# board.net
KiCad netlist of a schematic drawn in EAGLE
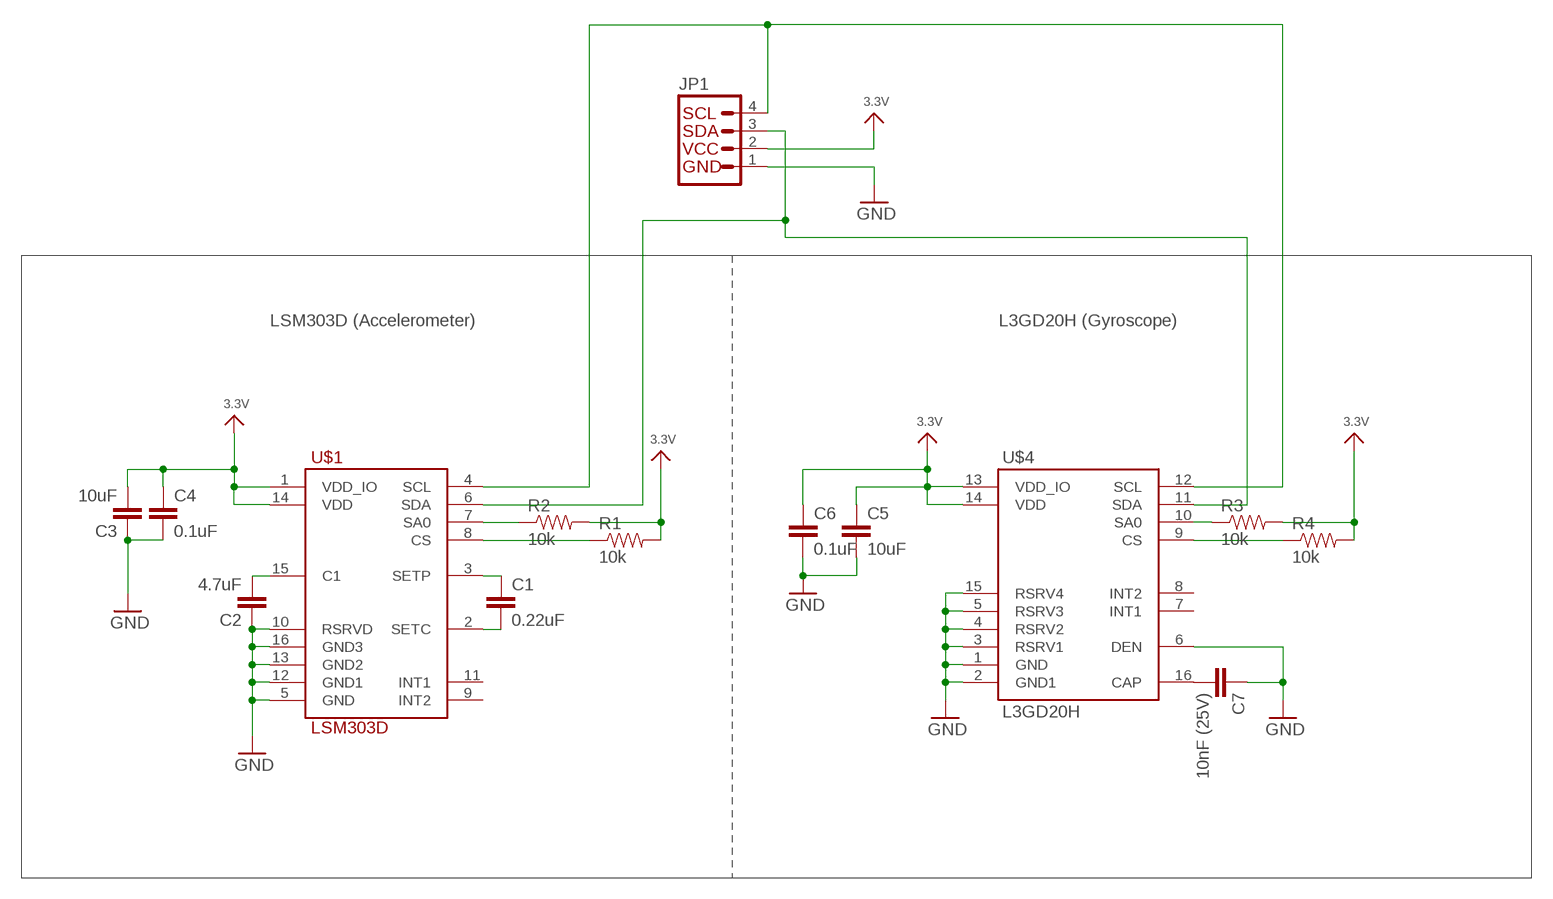
[diagram p0: schematic, sheet 1]

(export (version "E")
  (design (tool "Eeschema 10.0.6"))
  (components
    (comp (ref "C1")
      (value "0.22uF")
      (footprint "eagle-import:0805")
      (libsource (lib "eagle-import") (part "CAP0805"))
    )
    (comp (ref "C2")
      (value "4.7uF")
      (footprint "eagle-import:0805")
      (libsource (lib "eagle-import") (part "CAP0805"))
    )
    (comp (ref "C3")
      (value "10uF")
      (footprint "eagle-import:0805")
      (libsource (lib "eagle-import") (part "CAP0805"))
    )
    (comp (ref "C4")
      (value "0.1uF")
      (footprint "eagle-import:0805")
      (libsource (lib "eagle-import") (part "CAP0805"))
    )
    (comp (ref "C5")
      (value "10uF")
      (footprint "eagle-import:0805")
      (libsource (lib "eagle-import") (part "CAP0805"))
    )
    (comp (ref "C6")
      (value "0.1uF")
      (footprint "eagle-import:0805")
      (libsource (lib "eagle-import") (part "CAP0805"))
    )
    (comp (ref "C7")
      (value "10nF (25V)")
      (footprint "eagle-import:0805")
      (libsource (lib "eagle-import") (part "CAP0805"))
    )
    (comp (ref "JP1")
      (value "I2C_STANDARD")
      (footprint "eagle-import:1X04")
      (libsource (lib "eagle-import") (part "I2C_STANDARD"))
    )
    (comp (ref "R1")
      (value "10k")
      (footprint "eagle-import:0805")
      (libsource (lib "eagle-import") (part "RESISTOR0805-RES"))
    )
    (comp (ref "R2")
      (value "10k")
      (footprint "eagle-import:0805")
      (libsource (lib "eagle-import") (part "RESISTOR0805-RES"))
    )
    (comp (ref "R3")
      (value "10k")
      (footprint "eagle-import:0805")
      (libsource (lib "eagle-import") (part "RESISTOR0805-RES"))
    )
    (comp (ref "R4")
      (value "10k")
      (footprint "eagle-import:0805")
      (libsource (lib "eagle-import") (part "RESISTOR0805-RES"))
    )
    (comp (ref "U$1")
      (value "LSM303D")
      (footprint "eagle-import:LGA16_3X3MM")
      (libsource (lib "eagle-import") (part "LSM303D"))
    )
    (comp (ref "U$4")
      (value "L3GD20H")
      (footprint "eagle-import:LGA16_3X3MM")
      (libsource (lib "eagle-import") (part "L3GD20H"))
    )
  )
  (nets
    (net (code "1") (name "3.3V") (class "Default")
      (node (ref "C3") (pin "2") (pinfunction "2_2") (pintype "passive"))
      (node (ref "C4") (pin "1") (pinfunction "1_1") (pintype "passive"))
      (node (ref "C5") (pin "1") (pinfunction "1_1") (pintype "passive"))
      (node (ref "C6") (pin "1") (pinfunction "1_1") (pintype "passive"))
      (node (ref "JP1") (pin "2") (pinfunction "2_2") (pintype "passive"))
      (node (ref "R1") (pin "2") (pinfunction "2_2") (pintype "passive"))
      (node (ref "R2") (pin "2") (pinfunction "2_2") (pintype "passive"))
      (node (ref "R3") (pin "2") (pinfunction "2_2") (pintype "passive"))
      (node (ref "R4") (pin "2") (pinfunction "2_2") (pintype "passive"))
      (node (ref "U$1") (pin "1") (pinfunction "VDD_IO_1") (pintype "bidirectional"))
      (node (ref "U$1") (pin "14") (pinfunction "VDD_14") (pintype "bidirectional"))
      (node (ref "U$4") (pin "13") (pinfunction "VDD_IO_13") (pintype "bidirectional"))
      (node (ref "U$4") (pin "14") (pinfunction "VDD_14") (pintype "bidirectional"))
    )
    (net (code "2") (name "GND") (class "Default")
      (node (ref "C2") (pin "1") (pinfunction "1_1") (pintype "passive"))
      (node (ref "C3") (pin "1") (pinfunction "1_1") (pintype "passive"))
      (node (ref "C4") (pin "2") (pinfunction "2_2") (pintype "passive"))
      (node (ref "C5") (pin "2") (pinfunction "2_2") (pintype "passive"))
      (node (ref "C6") (pin "2") (pinfunction "2_2") (pintype "passive"))
      (node (ref "C7") (pin "1") (pinfunction "1_1") (pintype "passive"))
      (node (ref "JP1") (pin "1") (pinfunction "1_1") (pintype "passive"))
      (node (ref "U$1") (pin "10") (pinfunction "RSRVD_10") (pintype "bidirectional"))
      (node (ref "U$1") (pin "12") (pinfunction "GND1_12") (pintype "bidirectional"))
      (node (ref "U$1") (pin "13") (pinfunction "GND2_13") (pintype "bidirectional"))
      (node (ref "U$1") (pin "16") (pinfunction "GND3_16") (pintype "bidirectional"))
      (node (ref "U$1") (pin "5") (pinfunction "GND_5") (pintype "bidirectional"))
      (node (ref "U$4") (pin "1") (pinfunction "GND_1") (pintype "bidirectional"))
      (node (ref "U$4") (pin "15") (pinfunction "RSRV4_15") (pintype "bidirectional"))
      (node (ref "U$4") (pin "2") (pinfunction "GND1_2") (pintype "bidirectional"))
      (node (ref "U$4") (pin "3") (pinfunction "RSRV1_3") (pintype "bidirectional"))
      (node (ref "U$4") (pin "4") (pinfunction "RSRV2_4") (pintype "bidirectional"))
      (node (ref "U$4") (pin "5") (pinfunction "RSRV3_5") (pintype "bidirectional"))
      (node (ref "U$4") (pin "6") (pinfunction "DEN_6") (pintype "bidirectional"))
    )
    (net (code "3") (name "Net-(U$1-C1)") (class "Default")
      (node (ref "C2") (pin "2") (pinfunction "2_2") (pintype "passive"))
      (node (ref "U$1") (pin "15") (pinfunction "C1_15") (pintype "bidirectional"))
    )
    (net (code "4") (name "Net-(U$1-CS)") (class "Default")
      (node (ref "R1") (pin "1") (pinfunction "1_1") (pintype "passive"))
      (node (ref "U$1") (pin "8") (pinfunction "CS_8") (pintype "bidirectional"))
    )
    (net (code "5") (name "Net-(U$1-SA0)") (class "Default")
      (node (ref "R2") (pin "1") (pinfunction "1_1") (pintype "passive"))
      (node (ref "U$1") (pin "7") (pinfunction "SA0_7") (pintype "bidirectional"))
    )
    (net (code "6") (name "Net-(U$1-SCL)") (class "Default")
      (node (ref "JP1") (pin "4") (pinfunction "4_4") (pintype "passive"))
      (node (ref "U$1") (pin "4") (pinfunction "SCL_4") (pintype "bidirectional"))
      (node (ref "U$4") (pin "12") (pinfunction "SCL_12") (pintype "bidirectional"))
    )
    (net (code "7") (name "Net-(U$1-SDA)") (class "Default")
      (node (ref "JP1") (pin "3") (pinfunction "3_3") (pintype "passive"))
      (node (ref "U$1") (pin "6") (pinfunction "SDA_6") (pintype "bidirectional"))
      (node (ref "U$4") (pin "11") (pinfunction "SDA_11") (pintype "bidirectional"))
    )
    (net (code "8") (name "Net-(U$1-SETC)") (class "Default")
      (node (ref "C1") (pin "2") (pinfunction "2_2") (pintype "passive"))
      (node (ref "U$1") (pin "2") (pinfunction "SETC_2") (pintype "bidirectional"))
    )
    (net (code "9") (name "Net-(U$1-SETP)") (class "Default")
      (node (ref "C1") (pin "1") (pinfunction "1_1") (pintype "passive"))
      (node (ref "U$1") (pin "3") (pinfunction "SETP_3") (pintype "bidirectional"))
    )
    (net (code "10") (name "Net-(U$4-CAP)") (class "Default")
      (node (ref "C7") (pin "2") (pinfunction "2_2") (pintype "passive"))
      (node (ref "U$4") (pin "16") (pinfunction "CAP_16") (pintype "bidirectional"))
    )
    (net (code "11") (name "Net-(U$4-CS)") (class "Default")
      (node (ref "R4") (pin "1") (pinfunction "1_1") (pintype "passive"))
      (node (ref "U$4") (pin "9") (pinfunction "CS_9") (pintype "bidirectional"))
    )
    (net (code "12") (name "Net-(U$4-SA0)") (class "Default")
      (node (ref "R3") (pin "1") (pinfunction "1_1") (pintype "passive"))
      (node (ref "U$4") (pin "10") (pinfunction "SA0_10") (pintype "bidirectional"))
    )
    (net (code "13") (name "unconnected-(U$1-INT1-Pad11)") (class "Default")
      (node (ref "U$1") (pin "11") (pinfunction "INT1_11") (pintype "bidirectional"))
    )
    (net (code "14") (name "unconnected-(U$1-INT2-Pad9)") (class "Default")
      (node (ref "U$1") (pin "9") (pinfunction "INT2_9") (pintype "bidirectional"))
    )
    (net (code "15") (name "unconnected-(U$4-INT1-Pad7)") (class "Default")
      (node (ref "U$4") (pin "7") (pinfunction "INT1_7") (pintype "bidirectional"))
    )
    (net (code "16") (name "unconnected-(U$4-INT2-Pad8)") (class "Default")
      (node (ref "U$4") (pin "8") (pinfunction "INT2_8") (pintype "bidirectional"))
    )
  )
)
